# DigitalBoard.net
KiCad netlist of a schematic drawn in EAGLE
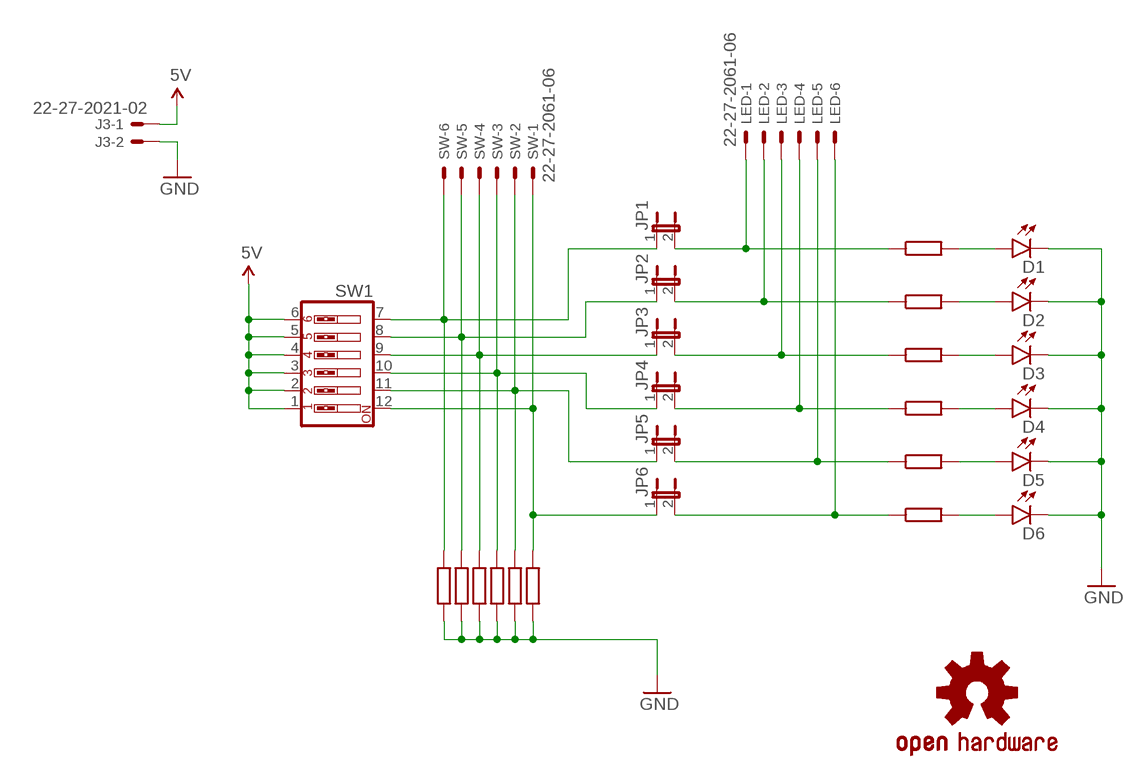
[diagram p0: schematic, sheet 1]

(export (version "E")
  (design (tool "Eeschema 10.0.6"))
  (components
    (comp (ref "D1")
      (value "LED5MM")
      (footprint "eagle-import:LED5MM")
      (libsource (lib "eagle-import") (part "LED5MM"))
    )
    (comp (ref "D2")
      (value "LED5MM")
      (footprint "eagle-import:LED5MM")
      (libsource (lib "eagle-import") (part "LED5MM"))
    )
    (comp (ref "D3")
      (value "LED5MM")
      (footprint "eagle-import:LED5MM")
      (libsource (lib "eagle-import") (part "LED5MM"))
    )
    (comp (ref "D4")
      (value "LED5MM")
      (footprint "eagle-import:LED5MM")
      (libsource (lib "eagle-import") (part "LED5MM"))
    )
    (comp (ref "D5")
      (value "LED5MM")
      (footprint "eagle-import:LED5MM")
      (libsource (lib "eagle-import") (part "LED5MM"))
    )
    (comp (ref "D6")
      (value "LED5MM")
      (footprint "eagle-import:LED5MM")
      (libsource (lib "eagle-import") (part "LED5MM"))
    )
    (comp (ref "J3")
      (value "22-27-2021-02")
      (footprint "eagle-import:6410-02")
      (libsource (lib "eagle-import") (part "22-?-0227-2021"))
    )
    (comp (ref "JP1")
      (value "JP1E")
      (footprint "eagle-import:JP1")
      (libsource (lib "eagle-import") (part "JP1E"))
    )
    (comp (ref "JP2")
      (value "JP1E")
      (footprint "eagle-import:JP1")
      (libsource (lib "eagle-import") (part "JP1E"))
    )
    (comp (ref "JP3")
      (value "JP1E")
      (footprint "eagle-import:JP1")
      (libsource (lib "eagle-import") (part "JP1E"))
    )
    (comp (ref "JP4")
      (value "JP1E")
      (footprint "eagle-import:JP1")
      (libsource (lib "eagle-import") (part "JP1E"))
    )
    (comp (ref "JP5")
      (value "JP1E")
      (footprint "eagle-import:JP1")
      (libsource (lib "eagle-import") (part "JP1E"))
    )
    (comp (ref "JP6")
      (value "JP1E")
      (footprint "eagle-import:JP1")
      (libsource (lib "eagle-import") (part "JP1E"))
    )
    (comp (ref "LED")
      (value "22-27-2061-06")
      (footprint "eagle-import:6410-06")
      (libsource (lib "eagle-import") (part "22-?-0627-2061"))
    )
    (comp (ref "LOGO1")
      (value "OSHW-LOGOS-COPPER")
      (footprint "eagle-import:OSHW-LOGO-S_COPPER")
      (libsource (lib "eagle-import") (part "OSHW-LOGOS-COPPER"))
    )
    (comp (ref "SW")
      (value "22-27-2061-06")
      (footprint "eagle-import:6410-06")
      (libsource (lib "eagle-import") (part "22-?-0627-2061"))
    )
    (comp (ref "SW1")
      (value "SW_DIP-6")
      (footprint "eagle-import:EDG-06")
      (libsource (lib "eagle-import") (part "SW_DIP-6"))
    )
  )
  (nets
    (net (code "1") (name "5V") (class "Default")
      (node (ref "J3") (pin "1") (pinfunction "S_1") (pintype "passive"))
      (node (ref "SW1") (pin "1") (pinfunction "1_1") (pintype "passive"))
      (node (ref "SW1") (pin "2") (pinfunction "2_2") (pintype "passive"))
      (node (ref "SW1") (pin "3") (pinfunction "3_3") (pintype "passive"))
      (node (ref "SW1") (pin "4") (pinfunction "4_4") (pintype "passive"))
      (node (ref "SW1") (pin "5") (pinfunction "5_5") (pintype "passive"))
      (node (ref "SW1") (pin "6") (pinfunction "6_6") (pintype "passive"))
    )
    (net (code "2") (name "GND") (class "Default")
      (node (ref "D1") (pin "K") (pinfunction "C_K") (pintype "passive"))
      (node (ref "D2") (pin "K") (pinfunction "C_K") (pintype "passive"))
      (node (ref "D3") (pin "K") (pinfunction "C_K") (pintype "passive"))
      (node (ref "D4") (pin "K") (pinfunction "C_K") (pintype "passive"))
      (node (ref "D5") (pin "K") (pinfunction "C_K") (pintype "passive"))
      (node (ref "D6") (pin "K") (pinfunction "C_K") (pintype "passive"))
      (node (ref "J3") (pin "2") (pinfunction "S_2") (pintype "passive"))
    )
    (net (code "3") (name "Net-(LEDA-S)") (class "Default")
      (node (ref "JP1") (pin "2") (pinfunction "2_2") (pintype "passive"))
      (node (ref "LED") (pin "1") (pinfunction "S_1") (pintype "passive"))
    )
    (net (code "4") (name "Net-(LEDB-S)") (class "Default")
      (node (ref "JP2") (pin "2") (pinfunction "2_2") (pintype "passive"))
      (node (ref "LED") (pin "2") (pinfunction "S_2") (pintype "passive"))
    )
    (net (code "5") (name "Net-(LEDC-S)") (class "Default")
      (node (ref "JP3") (pin "2") (pinfunction "2_2") (pintype "passive"))
      (node (ref "LED") (pin "3") (pinfunction "S_3") (pintype "passive"))
    )
    (net (code "6") (name "Net-(LEDD-S)") (class "Default")
      (node (ref "JP4") (pin "2") (pinfunction "2_2") (pintype "passive"))
      (node (ref "LED") (pin "4") (pinfunction "S_4") (pintype "passive"))
    )
    (net (code "7") (name "Net-(LEDE-S)") (class "Default")
      (node (ref "JP5") (pin "2") (pinfunction "2_2") (pintype "passive"))
      (node (ref "LED") (pin "5") (pinfunction "S_5") (pintype "passive"))
    )
    (net (code "8") (name "Net-(LEDF-S)") (class "Default")
      (node (ref "JP6") (pin "2") (pinfunction "2_2") (pintype "passive"))
      (node (ref "LED") (pin "6") (pinfunction "S_6") (pintype "passive"))
    )
    (net (code "9") (name "Net-(SWA-S)") (class "Default")
      (node (ref "JP6") (pin "1") (pinfunction "1_1") (pintype "passive"))
      (node (ref "SW") (pin "1") (pinfunction "S_1") (pintype "passive"))
      (node (ref "SW1") (pin "12") (pinfunction "12_12") (pintype "passive"))
    )
    (net (code "10") (name "Net-(SWB-S)") (class "Default")
      (node (ref "JP5") (pin "1") (pinfunction "1_1") (pintype "passive"))
      (node (ref "SW") (pin "2") (pinfunction "S_2") (pintype "passive"))
      (node (ref "SW1") (pin "11") (pinfunction "11_11") (pintype "passive"))
    )
    (net (code "11") (name "Net-(SWC-S)") (class "Default")
      (node (ref "JP4") (pin "1") (pinfunction "1_1") (pintype "passive"))
      (node (ref "SW") (pin "3") (pinfunction "S_3") (pintype "passive"))
      (node (ref "SW1") (pin "10") (pinfunction "10_10") (pintype "passive"))
    )
    (net (code "12") (name "Net-(SWD-S)") (class "Default")
      (node (ref "JP3") (pin "1") (pinfunction "1_1") (pintype "passive"))
      (node (ref "SW") (pin "4") (pinfunction "S_4") (pintype "passive"))
      (node (ref "SW1") (pin "9") (pinfunction "9_9") (pintype "passive"))
    )
    (net (code "13") (name "Net-(SWE-S)") (class "Default")
      (node (ref "JP2") (pin "1") (pinfunction "1_1") (pintype "passive"))
      (node (ref "SW") (pin "5") (pinfunction "S_5") (pintype "passive"))
      (node (ref "SW1") (pin "8") (pinfunction "8_8") (pintype "passive"))
    )
    (net (code "14") (name "Net-(SWF-S)") (class "Default")
      (node (ref "JP1") (pin "1") (pinfunction "1_1") (pintype "passive"))
      (node (ref "SW") (pin "6") (pinfunction "S_6") (pintype "passive"))
      (node (ref "SW1") (pin "7") (pinfunction "7_7") (pintype "passive"))
    )
    (net (code "15") (name "unconnected-(D1-PadA)") (class "Default")
      (node (ref "D1") (pin "A") (pinfunction "A_A") (pintype "passive"))
    )
    (net (code "16") (name "unconnected-(D2-PadA)") (class "Default")
      (node (ref "D2") (pin "A") (pinfunction "A_A") (pintype "passive"))
    )
    (net (code "17") (name "unconnected-(D3-PadA)") (class "Default")
      (node (ref "D3") (pin "A") (pinfunction "A_A") (pintype "passive"))
    )
    (net (code "18") (name "unconnected-(D4-PadA)") (class "Default")
      (node (ref "D4") (pin "A") (pinfunction "A_A") (pintype "passive"))
    )
    (net (code "19") (name "unconnected-(D5-PadA)") (class "Default")
      (node (ref "D5") (pin "A") (pinfunction "A_A") (pintype "passive"))
    )
    (net (code "20") (name "unconnected-(D6-PadA)") (class "Default")
      (node (ref "D6") (pin "A") (pinfunction "A_A") (pintype "passive"))
    )
  )
)
